# SCH_HackerCard_2024-12-08.net
KiCad netlist of a schematic drawn in EasyEDA
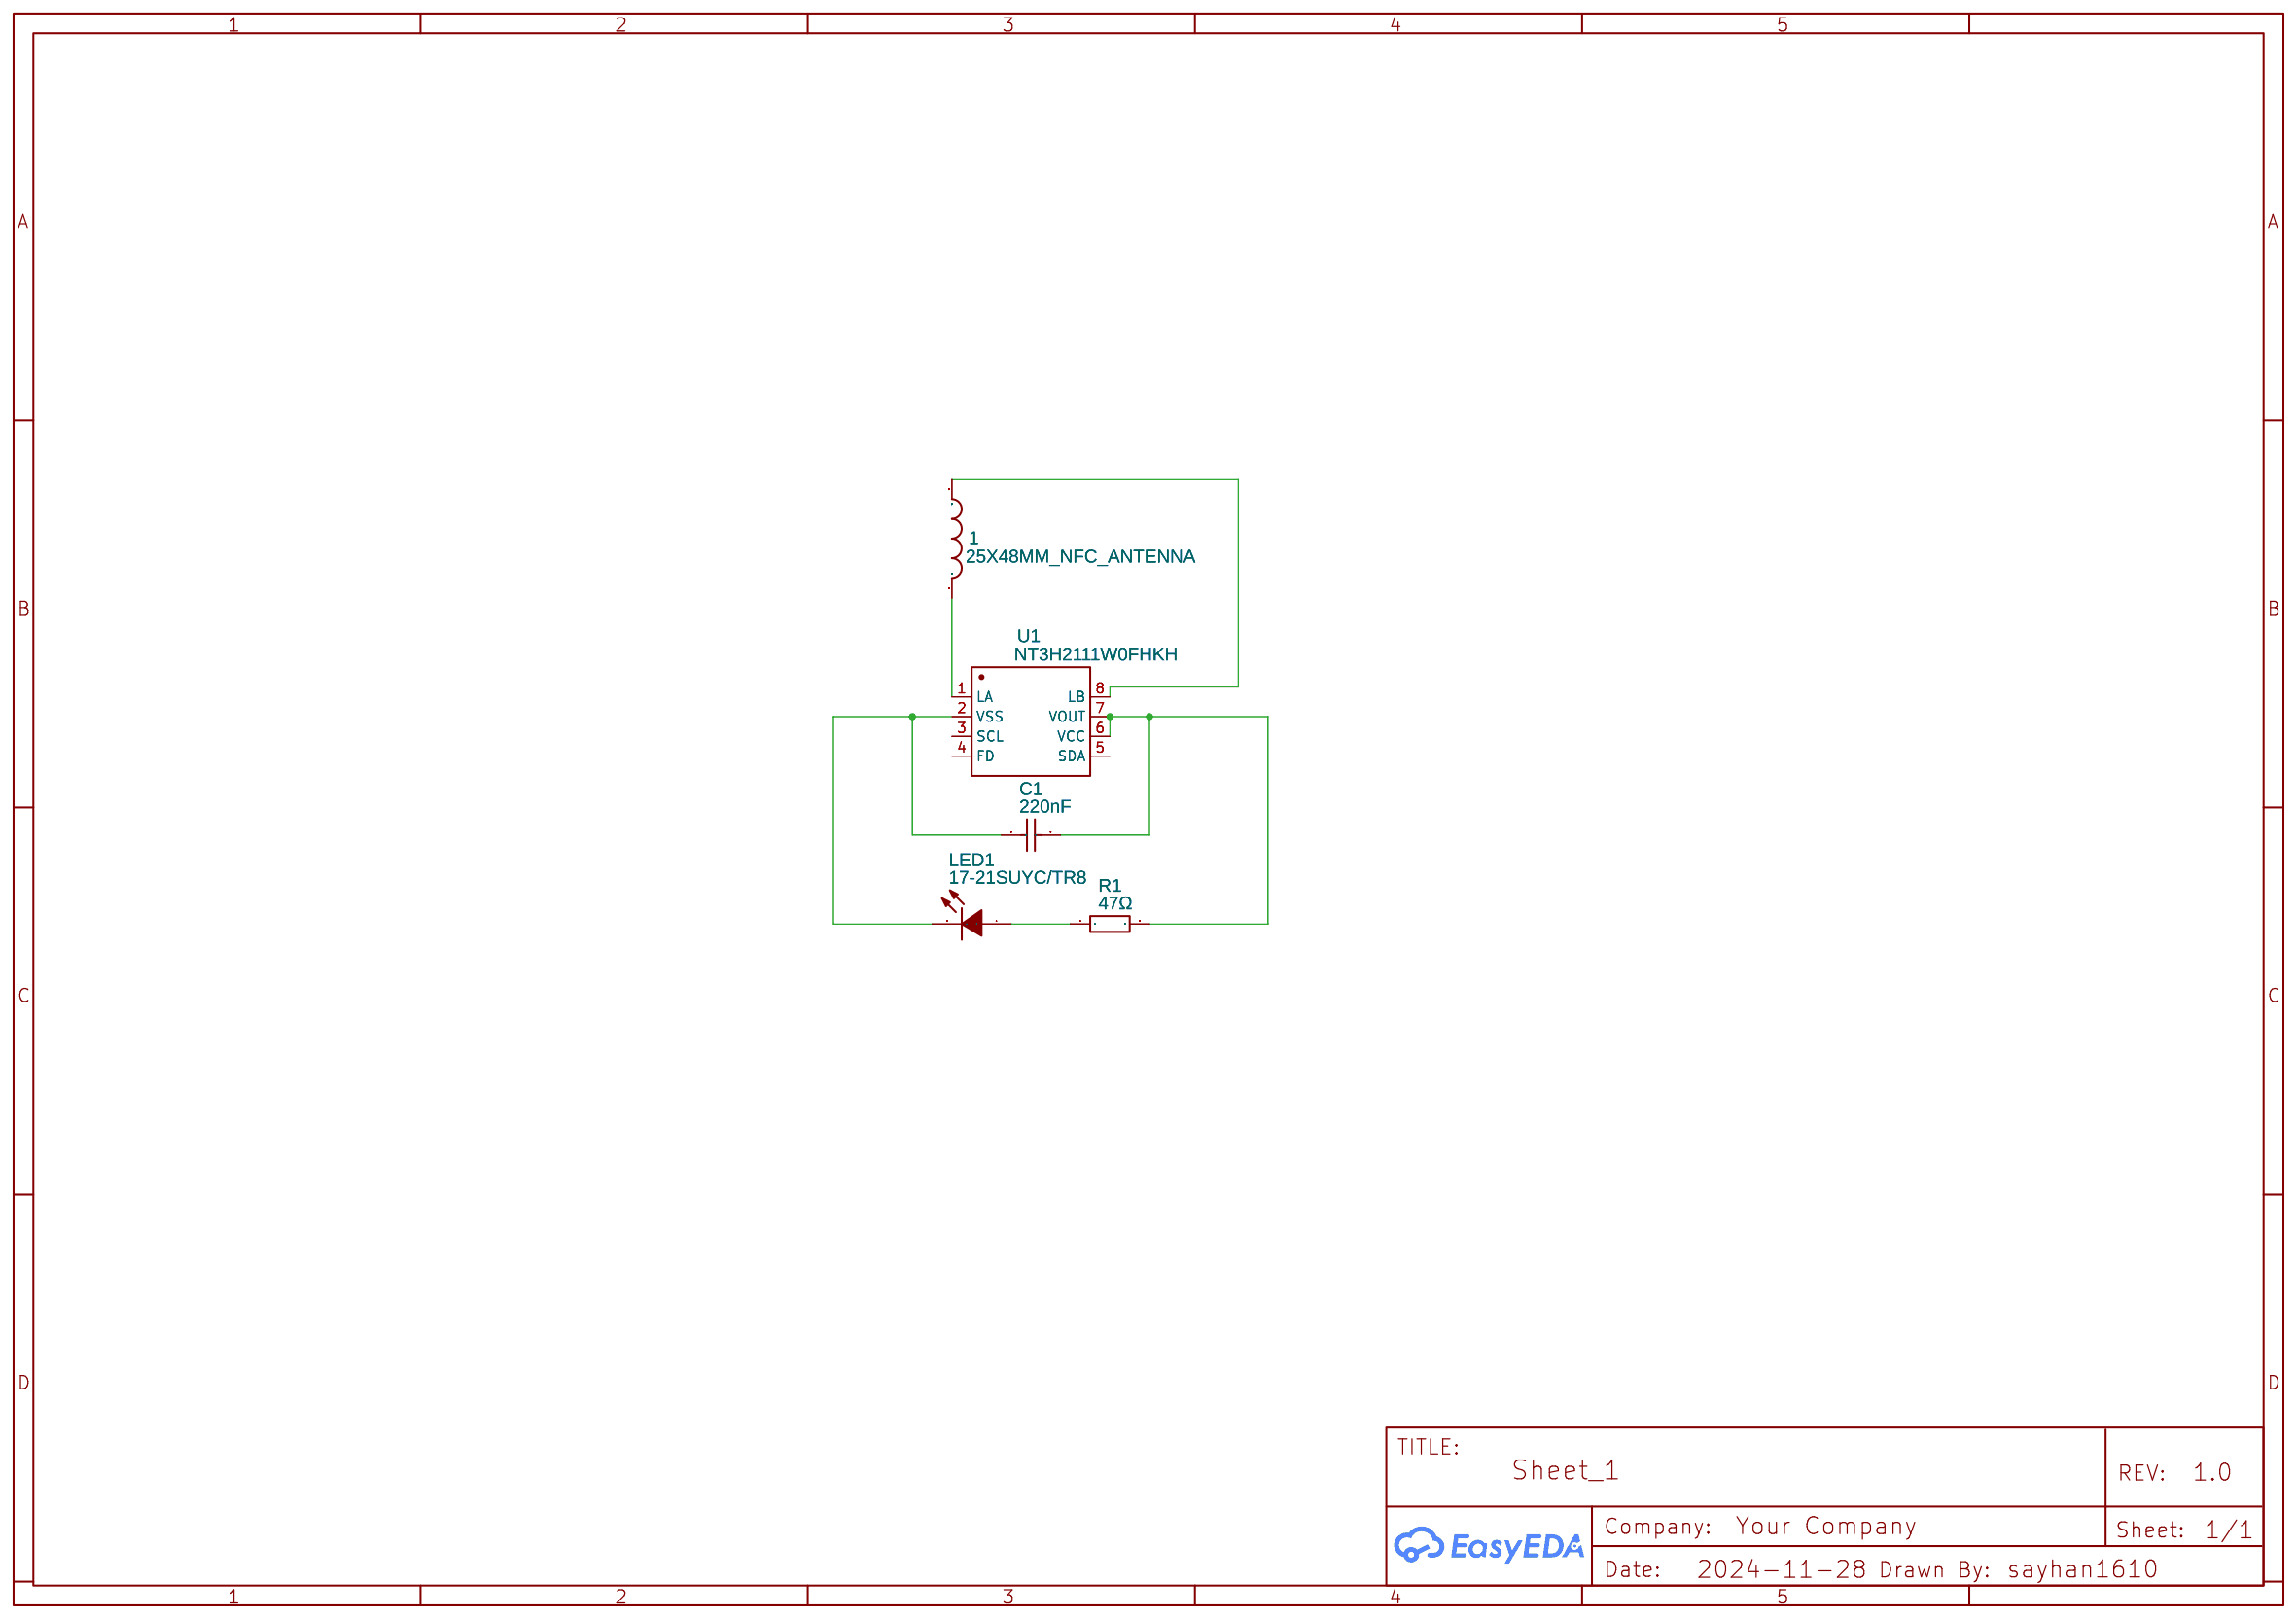
[diagram p0: schematic sheet]

(export (version "E")
  (design (tool "Eeschema 10.0.6"))
  (components
    (comp (ref "1") (value "25X48MM_NFC_ANTENNA") (libsource (lib "") (part "25X48MM_NFC_ANTENNA")))
    (comp (ref "C1")
      (value "220nF")
      (fields
        (field (name "Manufacturer Part") "CL10B224KA8NNNC")
        (field (name "Manufacturer") "SAMSUNG(三星)")
      )
      (libsource (lib "") (part "CL10B224KA8NNNC"))
    )
    (comp (ref "LED1")
      (value "17-21SUYC/TR8")
      (fields (field (name "Manufacturer Part") "KT-0805黄灯") (field (name "Manufacturer") "KENTO"))
      (libsource (lib "") (part "17-21SUYC/TR8"))
    )
    (comp (ref "R1")
      (value "47Ω")
      (fields
        (field (name "Manufacturer Part") "0603WAF470JT5E")
        (field (name "Manufacturer") "UNI-ROYAL(厚声)")
      )
      (libsource (lib "") (part "0603WAF470JT5E"))
    )
    (comp (ref "U1")
      (value "NT3H2111W0FHKH")
      (fields (field (name "Manufacturer") "NXP(恩智浦)"))
      (libsource (lib "") (part "NT3H2111W0FHKH"))
    )
  )
  (nets
    (net (code "1") (name "Net-(LED1-+)") (class "Default")
      (node (ref "LED1") (pin "1") (pinfunction "+_1") (pintype "unspecified"))
      (node (ref "R1") (pin "1") (pinfunction "1_1") (pintype "input"))
    )
    (net (code "2") (name "Net-(LED1--)") (class "Default")
      (node (ref "C1") (pin "1") (pinfunction "1_1") (pintype "input"))
      (node (ref "LED1") (pin "2") (pinfunction "-_2") (pintype "unspecified"))
      (node (ref "U1") (pin "2") (pinfunction "VSS_2") (pintype "unspecified"))
    )
    (net (code "3") (name "Net-(U1-LA)") (class "Default")
      (node (ref "1") (pin "P$2") (pinfunction "P$2_P$2") (pintype "bidirectional"))
      (node (ref "U1") (pin "1") (pinfunction "LA_1") (pintype "unspecified"))
    )
    (net (code "4") (name "Net-(U1-LB)") (class "Default")
      (node (ref "1") (pin "P$1") (pinfunction "P$1_P$1") (pintype "bidirectional"))
      (node (ref "U1") (pin "8") (pinfunction "LB_8") (pintype "unspecified"))
    )
    (net (code "5") (name "Net-(U1-VCC)") (class "Default")
      (node (ref "C1") (pin "2") (pinfunction "2_2") (pintype "input"))
      (node (ref "R1") (pin "2") (pinfunction "2_2") (pintype "input"))
      (node (ref "U1") (pin "6") (pinfunction "VCC_6") (pintype "unspecified"))
      (node (ref "U1") (pin "7") (pinfunction "VOUT_7") (pintype "unspecified"))
    )
    (net (code "6") (name "unconnected-(U1-FD-Pad4)") (class "Default")
      (node (ref "U1") (pin "4") (pinfunction "FD_4") (pintype "unspecified"))
    )
    (net (code "7") (name "unconnected-(U1-SCL-Pad3)") (class "Default")
      (node (ref "U1") (pin "3") (pinfunction "SCL_3") (pintype "unspecified"))
    )
    (net (code "8") (name "unconnected-(U1-SDA-Pad5)") (class "Default")
      (node (ref "U1") (pin "5") (pinfunction "SDA_5") (pintype "unspecified"))
    )
  )
)
